# SimpleNode31.net
KiCad netlist of a schematic drawn in Altium Designer
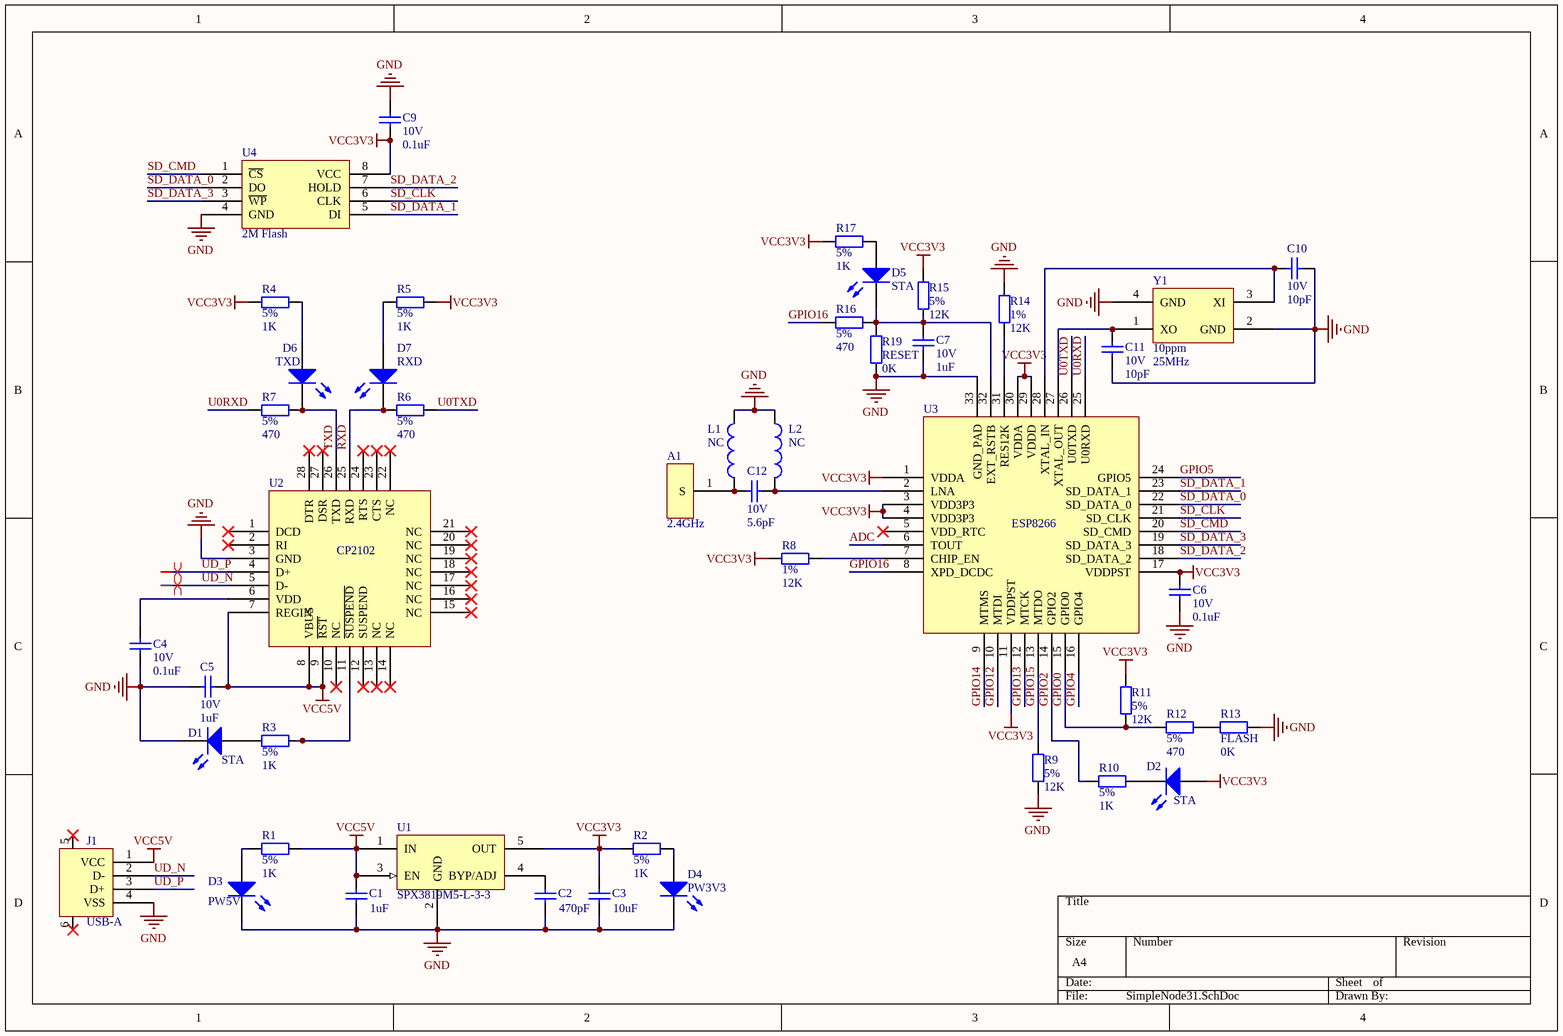
[diagram p0: SimpleNode31.SchDoc]

(export (version "E")
  (design (tool "Eeschema 10.0.6"))
  (components
    (comp (ref "A1")
      (value "2.4GHz")
      (footprint "AN9520-245")
      (description "贴片2.4G陶瓷天线")
      (libsource (lib "基础元器件") (part "AN9520-245"))
    )
    (comp (ref "C1")
      (value "1uF")
      (footprint "C0402")
      (description "贴片无极性电容")
      (fields (field (name "Comment") "105"))
      (libsource (lib "基础元器件") (part "贴片无极性电容"))
    )
    (comp (ref "C2")
      (value "470pF")
      (footprint "C0402")
      (description "贴片无极性电容")
      (fields (field (name "Comment") "CAP"))
      (libsource (lib "基础元器件") (part "贴片无极性电容"))
    )
    (comp (ref "C3")
      (value "10uF")
      (footprint "C0402")
      (description "贴片无极性电容")
      (fields (field (name "Comment") "CAP"))
      (libsource (lib "基础元器件") (part "贴片无极性电容"))
    )
    (comp (ref "C4")
      (value "10V")
      (footprint "C0402")
      (description "贴片无极性电容")
      (fields (field (name "ALTIUM_VALUE") "0.1uF"))
      (libsource (lib "基础元器件") (part "贴片无极性电容"))
    )
    (comp (ref "C5")
      (value "10V")
      (footprint "C0402")
      (description "贴片无极性电容")
      (fields (field (name "ALTIUM_VALUE") "1uF"))
      (libsource (lib "基础元器件") (part "贴片无极性电容"))
    )
    (comp (ref "C6")
      (value "10V")
      (footprint "C0402")
      (description "贴片无极性电容")
      (fields (field (name "ALTIUM_VALUE") "0.1uF"))
      (libsource (lib "基础元器件") (part "贴片无极性电容"))
    )
    (comp (ref "C7")
      (value "10V")
      (footprint "C0402")
      (description "贴片无极性电容")
      (fields (field (name "ALTIUM_VALUE") "1uF"))
      (libsource (lib "基础元器件") (part "贴片无极性电容"))
    )
    (comp (ref "C9")
      (value "10V")
      (footprint "C0402")
      (description "贴片无极性电容")
      (fields (field (name "ALTIUM_VALUE") "0.1uF"))
      (libsource (lib "基础元器件") (part "贴片无极性电容"))
    )
    (comp (ref "C10")
      (value "10V")
      (footprint "C0402")
      (description "贴片无极性电容")
      (fields (field (name "ALTIUM_VALUE") "10pF"))
      (libsource (lib "基础元器件") (part "贴片无极性电容"))
    )
    (comp (ref "C11")
      (value "10V")
      (footprint "C0402")
      (description "贴片无极性电容")
      (fields (field (name "ALTIUM_VALUE") "10pF"))
      (libsource (lib "基础元器件") (part "贴片无极性电容"))
    )
    (comp (ref "C12")
      (value "10V")
      (footprint "C0402")
      (description "贴片无极性电容")
      (fields (field (name "ALTIUM_VALUE") "5.6pF"))
      (libsource (lib "基础元器件") (part "贴片无极性电容"))
    )
    (comp (ref "D1")
      (value "STA")
      (footprint "LED0402")
      (description "贴片发光二级管")
      (libsource (lib "基础元器件") (part "贴片发光二级管"))
    )
    (comp (ref "D2")
      (value "STA")
      (footprint "LED0402")
      (description "贴片发光二级管")
      (libsource (lib "基础元器件") (part "贴片发光二级管"))
    )
    (comp (ref "D3")
      (value "PW5V")
      (footprint "LED0402")
      (description "贴片发光二级管")
      (libsource (lib "基础元器件") (part "贴片发光二级管"))
    )
    (comp (ref "D4")
      (value "PW3V3")
      (footprint "LED0402")
      (description "贴片发光二级管")
      (libsource (lib "基础元器件") (part "贴片发光二级管"))
    )
    (comp (ref "D5")
      (value "STA")
      (footprint "LED0402")
      (description "贴片发光二级管")
      (libsource (lib "基础元器件") (part "贴片发光二级管"))
    )
    (comp (ref "D6")
      (value "TXD")
      (footprint "LED0402")
      (description "贴片发光二级管")
      (libsource (lib "基础元器件") (part "贴片发光二级管"))
    )
    (comp (ref "D7")
      (value "RXD")
      (footprint "LED0402")
      (description "贴片发光二级管")
      (libsource (lib "基础元器件") (part "贴片发光二级管"))
    )
    (comp (ref "J1")
      (value "USB-A")
      (footprint "USB 2.0 Type A 公头 沉板")
      (description "USB-A 公头")
      (libsource (lib "基础连接件") (part "USB-A 公头"))
    )
    (comp (ref "L1")
      (value "NC")
      (footprint "L0402")
      (description "贴片电感")
      (libsource (lib "") (part "贴片电感_1"))
    )
    (comp (ref "L2")
      (value "NC")
      (footprint "L0402")
      (description "贴片电感")
      (libsource (lib "基础元器件") (part "贴片电感"))
    )
    (comp (ref "R1")
      (value "5%")
      (footprint "R0402")
      (description "贴片电阻")
      (fields (field (name "ALTIUM_VALUE") "1K"))
      (libsource (lib "基础元器件") (part "贴片电阻"))
    )
    (comp (ref "R2")
      (value "5%")
      (footprint "R0402")
      (description "贴片电阻")
      (fields (field (name "ALTIUM_VALUE") "1K"))
      (libsource (lib "基础元器件") (part "贴片电阻"))
    )
    (comp (ref "R3")
      (value "5%")
      (footprint "R0402")
      (description "贴片电阻")
      (fields (field (name "ALTIUM_VALUE") "1K"))
      (libsource (lib "基础元器件") (part "贴片电阻"))
    )
    (comp (ref "R4")
      (value "5%")
      (footprint "R0402")
      (description "贴片电阻")
      (fields (field (name "ALTIUM_VALUE") "1K"))
      (libsource (lib "基础元器件") (part "贴片电阻"))
    )
    (comp (ref "R5")
      (value "5%")
      (footprint "R0402")
      (description "贴片电阻")
      (fields (field (name "ALTIUM_VALUE") "1K"))
      (libsource (lib "基础元器件") (part "贴片电阻"))
    )
    (comp (ref "R6")
      (value "5%")
      (footprint "R0402")
      (description "贴片电阻")
      (fields (field (name "ALTIUM_VALUE") "470"))
      (libsource (lib "基础元器件") (part "贴片电阻"))
    )
    (comp (ref "R7")
      (value "5%")
      (footprint "R0402")
      (description "贴片电阻")
      (fields (field (name "ALTIUM_VALUE") "470"))
      (libsource (lib "基础元器件") (part "贴片电阻"))
    )
    (comp (ref "R8")
      (value "1%")
      (footprint "R0402")
      (description "贴片电阻")
      (fields (field (name "ALTIUM_VALUE") "12K"))
      (libsource (lib "") (part "贴片电阻_1"))
    )
    (comp (ref "R9")
      (value "5%")
      (footprint "R0402")
      (description "贴片电阻")
      (fields (field (name "ALTIUM_VALUE") "12K"))
      (libsource (lib "") (part "贴片电阻_2"))
    )
    (comp (ref "R10")
      (value "5%")
      (footprint "R0402")
      (description "贴片电阻")
      (fields (field (name "ALTIUM_VALUE") "1K"))
      (libsource (lib "基础元器件") (part "贴片电阻"))
    )
    (comp (ref "R11")
      (value "5%")
      (footprint "R0402")
      (description "贴片电阻")
      (fields (field (name "ALTIUM_VALUE") "12K"))
      (libsource (lib "") (part "贴片电阻_2"))
    )
    (comp (ref "R12")
      (value "5%")
      (footprint "R0402")
      (description "贴片电阻")
      (fields (field (name "ALTIUM_VALUE") "470"))
      (libsource (lib "") (part "贴片电阻_1"))
    )
    (comp (ref "R13")
      (value "FLASH")
      (footprint "R0402")
      (description "贴片电阻")
      (fields (field (name "ALTIUM_VALUE") "0K"))
      (libsource (lib "基础元器件") (part "贴片电阻"))
    )
    (comp (ref "R14")
      (value "1%")
      (footprint "R0402")
      (description "贴片电阻")
      (fields (field (name "ALTIUM_VALUE") "12K"))
      (libsource (lib "") (part "贴片电阻_2"))
    )
    (comp (ref "R15")
      (value "5%")
      (footprint "R0402")
      (description "贴片电阻")
      (fields (field (name "ALTIUM_VALUE") "12K"))
      (libsource (lib "") (part "贴片电阻_2"))
    )
    (comp (ref "R16")
      (value "5%")
      (footprint "R0402")
      (description "贴片电阻")
      (fields (field (name "ALTIUM_VALUE") "470"))
      (libsource (lib "基础元器件") (part "贴片电阻"))
    )
    (comp (ref "R17")
      (value "5%")
      (footprint "R0402")
      (description "贴片电阻")
      (fields (field (name "ALTIUM_VALUE") "1K"))
      (libsource (lib "") (part "贴片电阻_1"))
    )
    (comp (ref "R19")
      (value "RESET")
      (footprint "R0402")
      (description "贴片电阻")
      (fields (field (name "ALTIUM_VALUE") "0K"))
      (libsource (lib "") (part "贴片电阻_2"))
    )
    (comp (ref "U1")
      (value "SPX3819M5-L-3-3")
      (footprint "SOT25-5")
      (description "贴片5V转3.3V芯片")
      (libsource (lib "基础元器件") (part "SPX3819M5-L-3-3"))
    )
    (comp (ref "U2")
      (value "CP2102")
      (footprint "MLP28")
      (description "贴片USB转TTL")
      (libsource (lib "基础元器件") (part "CP2102"))
    )
    (comp (ref "U3")
      (value "ESP8266")
      (footprint "QFN32L")
      (description "ESP8266无线WiFi芯片")
      (libsource (lib "基础元器件") (part "ESP8266"))
    )
    (comp (ref "U4")
      (value "2M Flash")
      (footprint "SOP8")
      (description "贴片2M存储Flash芯片")
      (libsource (lib "基础元器件") (part "GD25Q16CSIG"))
    )
    (comp (ref "Y1")
      (value "10ppm")
      (footprint "XTAL-2520")
      (description "贴片无源晶振")
      (fields (field (name "ALTIUM_VALUE") "25MHz"))
      (libsource (lib "基础元器件") (part "贴片无源晶振"))
    )
  )
  (nets
    (net (code "1") (name "/ADC") (class "Default")
      (node (ref "U3") (pin "6") (pinfunction "TOUT_6") (pintype "passive"))
    )
    (net (code "2") (name "/GPIO0") (class "Default")
      (node (ref "R11") (pin "1") (pinfunction "1_1") (pintype "passive"))
      (node (ref "R12") (pin "1") (pinfunction "1_1") (pintype "passive"))
      (node (ref "U3") (pin "15") (pinfunction "GPIO0_15") (pintype "passive"))
    )
    (net (code "3") (name "/GPIO2") (class "Default")
      (node (ref "R10") (pin "2") (pinfunction "2_2") (pintype "passive"))
      (node (ref "U3") (pin "14") (pinfunction "GPIO2_14") (pintype "passive"))
    )
    (net (code "4") (name "/GPIO4") (class "Default")
      (node (ref "U3") (pin "16") (pinfunction "GPIO4_16") (pintype "passive"))
    )
    (net (code "5") (name "/GPIO5") (class "Default")
      (node (ref "U3") (pin "24") (pinfunction "GPIO5_24") (pintype "passive"))
    )
    (net (code "6") (name "/GPIO12") (class "Default")
      (node (ref "U3") (pin "10") (pinfunction "MTDI_10") (pintype "passive"))
    )
    (net (code "7") (name "/GPIO13") (class "Default")
      (node (ref "U3") (pin "12") (pinfunction "MTCK_12") (pintype "passive"))
    )
    (net (code "8") (name "/GPIO14") (class "Default")
      (node (ref "U3") (pin "9") (pinfunction "MTMS_9") (pintype "passive"))
    )
    (net (code "9") (name "/GPIO15") (class "Default")
      (node (ref "R9") (pin "2") (pinfunction "2_2") (pintype "passive"))
      (node (ref "U3") (pin "13") (pinfunction "MTDO_13") (pintype "passive"))
    )
    (net (code "10") (name "/GPIO16") (class "Default")
      (node (ref "R16") (pin "2") (pinfunction "2_2") (pintype "passive"))
      (node (ref "U3") (pin "8") (pinfunction "XPD_DCDC_8") (pintype "passive"))
    )
    (net (code "11") (name "/RXD") (class "Default")
      (node (ref "D7") (pin "2") (pinfunction "K_2") (pintype "passive"))
      (node (ref "R6") (pin "2") (pinfunction "2_2") (pintype "passive"))
      (node (ref "U2") (pin "25") (pinfunction "RXD_25") (pintype "passive"))
    )
    (net (code "12") (name "/SD_CLK") (class "Default")
      (node (ref "U3") (pin "21") (pinfunction "SD_CLK_21") (pintype "passive"))
      (node (ref "U4") (pin "6") (pinfunction "CLK_6") (pintype "passive"))
    )
    (net (code "13") (name "/SD_CMD") (class "Default")
      (node (ref "U3") (pin "20") (pinfunction "SD_CMD_20") (pintype "passive"))
      (node (ref "U4") (pin "1") (pinfunction "~{CS}_1") (pintype "passive"))
    )
    (net (code "14") (name "/SD_DATA_0") (class "Default")
      (node (ref "U3") (pin "22") (pinfunction "SD_DATA_0_22") (pintype "passive"))
      (node (ref "U4") (pin "2") (pinfunction "DO_2") (pintype "passive"))
    )
    (net (code "15") (name "/SD_DATA_1") (class "Default")
      (node (ref "U3") (pin "23") (pinfunction "SD_DATA_1_23") (pintype "passive"))
      (node (ref "U4") (pin "5") (pinfunction "DI_5") (pintype "passive"))
    )
    (net (code "16") (name "/SD_DATA_2") (class "Default")
      (node (ref "U3") (pin "18") (pinfunction "SD_DATA_2_18") (pintype "passive"))
      (node (ref "U4") (pin "7") (pinfunction "HOLD_7") (pintype "passive"))
    )
    (net (code "17") (name "/SD_DATA_3") (class "Default")
      (node (ref "U3") (pin "19") (pinfunction "SD_DATA_3_19") (pintype "passive"))
      (node (ref "U4") (pin "3") (pinfunction "~{WP}_3") (pintype "passive"))
    )
    (net (code "18") (name "/TXD") (class "Default")
      (node (ref "D6") (pin "2") (pinfunction "K_2") (pintype "passive"))
      (node (ref "R7") (pin "1") (pinfunction "1_1") (pintype "passive"))
      (node (ref "U2") (pin "26") (pinfunction "TXD_26") (pintype "passive"))
    )
    (net (code "19") (name "/U0RXD") (class "Default")
      (node (ref "R7") (pin "2") (pinfunction "2_2") (pintype "passive"))
      (node (ref "U3") (pin "25") (pinfunction "U0RXD_25") (pintype "passive"))
    )
    (net (code "20") (name "/U0TXD") (class "Default")
      (node (ref "R6") (pin "1") (pinfunction "1_1") (pintype "passive"))
      (node (ref "U3") (pin "26") (pinfunction "U0TXD_26") (pintype "passive"))
    )
    (net (code "21") (name "/UD_N") (class "Default")
      (node (ref "J1") (pin "2") (pinfunction "D-_2") (pintype "passive"))
      (node (ref "U2") (pin "5") (pinfunction "D-_5") (pintype "passive"))
    )
    (net (code "22") (name "/UD_P") (class "Default")
      (node (ref "J1") (pin "3") (pinfunction "D+_3") (pintype "passive"))
      (node (ref "U2") (pin "4") (pinfunction "D+_4") (pintype "passive"))
    )
    (net (code "23") (name "GND") (class "Default")
      (node (ref "C1") (pin "1") (pinfunction "1_1") (pintype "passive"))
      (node (ref "C10") (pin "2") (pinfunction "2_2") (pintype "passive"))
      (node (ref "C11") (pin "2") (pinfunction "2_2") (pintype "passive"))
      (node (ref "C2") (pin "1") (pinfunction "1_1") (pintype "passive"))
      (node (ref "C3") (pin "1") (pinfunction "1_1") (pintype "passive"))
      (node (ref "C4") (pin "1") (pinfunction "1_1") (pintype "passive"))
      (node (ref "C5") (pin "2") (pinfunction "2_2") (pintype "passive"))
      (node (ref "C6") (pin "1") (pinfunction "1_1") (pintype "passive"))
      (node (ref "C7") (pin "1") (pinfunction "1_1") (pintype "passive"))
      (node (ref "C9") (pin "1") (pinfunction "1_1") (pintype "passive"))
      (node (ref "D1") (pin "2") (pinfunction "K_2") (pintype "passive"))
      (node (ref "D3") (pin "2") (pinfunction "K_2") (pintype "passive"))
      (node (ref "D4") (pin "2") (pinfunction "K_2") (pintype "passive"))
      (node (ref "J1") (pin "4") (pinfunction "VSS_4") (pintype "passive"))
      (node (ref "L1") (pin "2") (pinfunction "2_2") (pintype "passive"))
      (node (ref "L2") (pin "2") (pinfunction "2_2") (pintype "passive"))
      (node (ref "R13") (pin "1") (pinfunction "1_1") (pintype "passive"))
      (node (ref "R14") (pin "2") (pinfunction "2_2") (pintype "passive"))
      (node (ref "R19") (pin "1") (pinfunction "1_1") (pintype "passive"))
      (node (ref "R9") (pin "1") (pinfunction "1_1") (pintype "passive"))
      (node (ref "U1") (pin "2") (pinfunction "GND_2") (pintype "power_in"))
      (node (ref "U2") (pin "3") (pinfunction "GND_3") (pintype "passive"))
      (node (ref "U3") (pin "33") (pinfunction "GND_PAD_33") (pintype "passive"))
      (node (ref "U4") (pin "4") (pinfunction "GND_4") (pintype "passive"))
      (node (ref "Y1") (pin "2") (pinfunction "GND_2") (pintype "passive"))
      (node (ref "Y1") (pin "4") (pinfunction "GND_4") (pintype "passive"))
    )
    (net (code "24") (name "Net-(A1-S)") (class "Default")
      (node (ref "A1") (pin "1") (pinfunction "S_1") (pintype "passive"))
      (node (ref "C12") (pin "1") (pinfunction "1_1") (pintype "passive"))
      (node (ref "L1") (pin "1") (pinfunction "1_1") (pintype "passive"))
    )
    (net (code "25") (name "Net-(D1-A)") (class "Default")
      (node (ref "D1") (pin "1") (pinfunction "A_1") (pintype "passive"))
      (node (ref "R3") (pin "2") (pinfunction "2_2") (pintype "passive"))
    )
    (net (code "26") (name "Net-(D2-K)") (class "Default")
      (node (ref "D2") (pin "2") (pinfunction "K_2") (pintype "passive"))
      (node (ref "R10") (pin "1") (pinfunction "1_1") (pintype "passive"))
    )
    (net (code "27") (name "Net-(D3-A)") (class "Default")
      (node (ref "D3") (pin "1") (pinfunction "A_1") (pintype "passive"))
      (node (ref "R1") (pin "2") (pinfunction "2_2") (pintype "passive"))
    )
    (net (code "28") (name "Net-(D4-A)") (class "Default")
      (node (ref "D4") (pin "1") (pinfunction "A_1") (pintype "passive"))
      (node (ref "R2") (pin "1") (pinfunction "1_1") (pintype "passive"))
    )
    (net (code "29") (name "Net-(D5-A)") (class "Default")
      (node (ref "D5") (pin "1") (pinfunction "A_1") (pintype "passive"))
      (node (ref "R17") (pin "2") (pinfunction "2_2") (pintype "passive"))
    )
    (net (code "30") (name "Net-(D5-K)") (class "Default")
      (node (ref "C7") (pin "2") (pinfunction "2_2") (pintype "passive"))
      (node (ref "D5") (pin "2") (pinfunction "K_2") (pintype "passive"))
      (node (ref "R15") (pin "1") (pinfunction "1_1") (pintype "passive"))
      (node (ref "R16") (pin "1") (pinfunction "1_1") (pintype "passive"))
      (node (ref "R19") (pin "2") (pinfunction "2_2") (pintype "passive"))
      (node (ref "U3") (pin "32") (pinfunction "EXT_RSTB_32") (pintype "passive"))
    )
    (net (code "31") (name "Net-(D6-A)") (class "Default")
      (node (ref "D6") (pin "1") (pinfunction "A_1") (pintype "passive"))
      (node (ref "R4") (pin "1") (pinfunction "1_1") (pintype "passive"))
    )
    (net (code "32") (name "Net-(D7-A)") (class "Default")
      (node (ref "D7") (pin "1") (pinfunction "A_1") (pintype "passive"))
      (node (ref "R5") (pin "2") (pinfunction "2_2") (pintype "passive"))
    )
    (net (code "33") (name "Net-(R12-Pad2)") (class "Default")
      (node (ref "R12") (pin "2") (pinfunction "2_2") (pintype "passive"))
      (node (ref "R13") (pin "2") (pinfunction "2_2") (pintype "passive"))
    )
    (net (code "34") (name "Net-(U1-BYP{slash}ADJ)") (class "Default")
      (node (ref "C2") (pin "2") (pinfunction "2_2") (pintype "passive"))
      (node (ref "U1") (pin "4") (pinfunction "BYP/ADJ_4") (pintype "passive"))
    )
    (net (code "35") (name "Net-(U2-VDD)") (class "Default")
      (node (ref "C4") (pin "2") (pinfunction "2_2") (pintype "passive"))
      (node (ref "U2") (pin "6") (pinfunction "VDD_6") (pintype "passive"))
    )
    (net (code "36") (name "Net-(U2-~{SUSPEND})") (class "Default")
      (node (ref "R3") (pin "1") (pinfunction "1_1") (pintype "passive"))
      (node (ref "U2") (pin "11") (pinfunction "~{SUSPEND}_11") (pintype "passive"))
    )
    (net (code "37") (name "Net-(U3-CHIP_EN)") (class "Default")
      (node (ref "R8") (pin "2") (pinfunction "2_2") (pintype "passive"))
      (node (ref "U3") (pin "7") (pinfunction "CHIP_EN_7") (pintype "passive"))
    )
    (net (code "38") (name "Net-(U3-LNA)") (class "Default")
      (node (ref "C12") (pin "2") (pinfunction "2_2") (pintype "passive"))
      (node (ref "L2") (pin "1") (pinfunction "1_1") (pintype "passive"))
      (node (ref "U3") (pin "2") (pinfunction "LNA_2") (pintype "passive"))
    )
    (net (code "39") (name "Net-(U3-RES12K)") (class "Default")
      (node (ref "R14") (pin "1") (pinfunction "1_1") (pintype "passive"))
      (node (ref "U3") (pin "31") (pinfunction "RES12K_31") (pintype "passive"))
    )
    (net (code "40") (name "Net-(U3-XTAL_IN)") (class "Default")
      (node (ref "C10") (pin "1") (pinfunction "1_1") (pintype "passive"))
      (node (ref "U3") (pin "28") (pinfunction "XTAL_IN_28") (pintype "passive"))
      (node (ref "Y1") (pin "3") (pinfunction "XI_3") (pintype "passive"))
    )
    (net (code "41") (name "Net-(U3-XTAL_OUT)") (class "Default")
      (node (ref "C11") (pin "1") (pinfunction "1_1") (pintype "passive"))
      (node (ref "U3") (pin "27") (pinfunction "XTAL_OUT_27") (pintype "passive"))
      (node (ref "Y1") (pin "1") (pinfunction "XO_1") (pintype "passive"))
    )
    (net (code "42") (name "VCC3V3") (class "Default")
      (node (ref "C3") (pin "2") (pinfunction "2_2") (pintype "passive"))
      (node (ref "C6") (pin "2") (pinfunction "2_2") (pintype "passive"))
      (node (ref "C9") (pin "2") (pinfunction "2_2") (pintype "passive"))
      (node (ref "D2") (pin "1") (pinfunction "A_1") (pintype "passive"))
      (node (ref "R11") (pin "2") (pinfunction "2_2") (pintype "passive"))
      (node (ref "R15") (pin "2") (pinfunction "2_2") (pintype "passive"))
      (node (ref "R17") (pin "1") (pinfunction "1_1") (pintype "passive"))
      (node (ref "R2") (pin "2") (pinfunction "2_2") (pintype "passive"))
      (node (ref "R4") (pin "2") (pinfunction "2_2") (pintype "passive"))
      (node (ref "R5") (pin "1") (pinfunction "1_1") (pintype "passive"))
      (node (ref "R8") (pin "1") (pinfunction "1_1") (pintype "passive"))
      (node (ref "U1") (pin "5") (pinfunction "OUT_5") (pintype "power_in"))
      (node (ref "U3") (pin "1") (pinfunction "VDDA_1") (pintype "passive"))
      (node (ref "U3") (pin "11") (pinfunction "VDDPST_11") (pintype "passive"))
      (node (ref "U3") (pin "17") (pinfunction "VDDPST_17") (pintype "passive"))
      (node (ref "U3") (pin "29") (pinfunction "VDDD_29") (pintype "passive"))
      (node (ref "U3") (pin "3") (pinfunction "VDD3P3_3") (pintype "passive"))
      (node (ref "U3") (pin "30") (pinfunction "VDDA_30") (pintype "passive"))
      (node (ref "U3") (pin "4") (pinfunction "VDD3P3_4") (pintype "passive"))
      (node (ref "U4") (pin "8") (pinfunction "VCC_8") (pintype "power_in"))
    )
    (net (code "43") (name "VCC5V") (class "Default")
      (node (ref "C1") (pin "2") (pinfunction "2_2") (pintype "passive"))
      (node (ref "C5") (pin "1") (pinfunction "1_1") (pintype "passive"))
      (node (ref "J1") (pin "1") (pinfunction "VCC_1") (pintype "passive"))
      (node (ref "R1") (pin "1") (pinfunction "1_1") (pintype "passive"))
      (node (ref "U1") (pin "1") (pinfunction "IN_1") (pintype "power_in"))
      (node (ref "U1") (pin "3") (pinfunction "EN_3") (pintype "input"))
      (node (ref "U2") (pin "7") (pinfunction "REGIN_7") (pintype "passive"))
      (node (ref "U2") (pin "8") (pinfunction "VBUS_8") (pintype "passive"))
      (node (ref "U2") (pin "9") (pinfunction "~{RST}_9") (pintype "passive"))
    )
    (net (code "44") (name "unconnected-(J1-Pad5)") (class "Default")
      (node (ref "J1") (pin "5") (pinfunction "5_5") (pintype "passive+no_connect"))
    )
    (net (code "45") (name "unconnected-(J1-Pad6)") (class "Default")
      (node (ref "J1") (pin "6") (pinfunction "6_6") (pintype "passive+no_connect"))
    )
    (net (code "46") (name "unconnected-(U2-CTS-Pad23)") (class "Default")
      (node (ref "U2") (pin "23") (pinfunction "CTS_23") (pintype "passive+no_connect"))
    )
    (net (code "47") (name "unconnected-(U2-DCD-Pad1)") (class "Default")
      (node (ref "U2") (pin "1") (pinfunction "DCD_1") (pintype "passive+no_connect"))
    )
    (net (code "48") (name "unconnected-(U2-DSR-Pad27)") (class "Default")
      (node (ref "U2") (pin "27") (pinfunction "DSR_27") (pintype "passive+no_connect"))
    )
    (net (code "49") (name "unconnected-(U2-DTR-Pad28)") (class "Default")
      (node (ref "U2") (pin "28") (pinfunction "DTR_28") (pintype "passive+no_connect"))
    )
    (net (code "50") (name "unconnected-(U2-NC-Pad10)") (class "Default")
      (node (ref "U2") (pin "10") (pinfunction "NC_10") (pintype "passive+no_connect"))
    )
    (net (code "51") (name "unconnected-(U2-NC-Pad13)") (class "Default")
      (node (ref "U2") (pin "13") (pinfunction "NC_13") (pintype "passive+no_connect"))
    )
    (net (code "52") (name "unconnected-(U2-NC-Pad14)") (class "Default")
      (node (ref "U2") (pin "14") (pinfunction "NC_14") (pintype "passive+no_connect"))
    )
    (net (code "53") (name "unconnected-(U2-NC-Pad15)") (class "Default")
      (node (ref "U2") (pin "15") (pinfunction "NC_15") (pintype "passive+no_connect"))
    )
    (net (code "54") (name "unconnected-(U2-NC-Pad16)") (class "Default")
      (node (ref "U2") (pin "16") (pinfunction "NC_16") (pintype "passive+no_connect"))
    )
    (net (code "55") (name "unconnected-(U2-NC-Pad17)") (class "Default")
      (node (ref "U2") (pin "17") (pinfunction "NC_17") (pintype "passive+no_connect"))
    )
    (net (code "56") (name "unconnected-(U2-NC-Pad18)") (class "Default")
      (node (ref "U2") (pin "18") (pinfunction "NC_18") (pintype "passive+no_connect"))
    )
    (net (code "57") (name "unconnected-(U2-NC-Pad19)") (class "Default")
      (node (ref "U2") (pin "19") (pinfunction "NC_19") (pintype "passive+no_connect"))
    )
    (net (code "58") (name "unconnected-(U2-NC-Pad20)") (class "Default")
      (node (ref "U2") (pin "20") (pinfunction "NC_20") (pintype "passive+no_connect"))
    )
    (net (code "59") (name "unconnected-(U2-NC-Pad21)") (class "Default")
      (node (ref "U2") (pin "21") (pinfunction "NC_21") (pintype "passive+no_connect"))
    )
    (net (code "60") (name "unconnected-(U2-NC-Pad22)") (class "Default")
      (node (ref "U2") (pin "22") (pinfunction "NC_22") (pintype "passive+no_connect"))
    )
    (net (code "61") (name "unconnected-(U2-RI-Pad2)") (class "Default")
      (node (ref "U2") (pin "2") (pinfunction "RI_2") (pintype "passive+no_connect"))
    )
    (net (code "62") (name "unconnected-(U2-RTS-Pad24)") (class "Default")
      (node (ref "U2") (pin "24") (pinfunction "RTS_24") (pintype "passive+no_connect"))
    )
    (net (code "63") (name "unconnected-(U2-SUSPEND-Pad12)") (class "Default")
      (node (ref "U2") (pin "12") (pinfunction "SUSPEND_12") (pintype "passive+no_connect"))
    )
    (net (code "64") (name "unconnected-(U3-VDD_RTC-Pad5)") (class "Default")
      (node (ref "U3") (pin "5") (pinfunction "VDD_RTC_5") (pintype "passive+no_connect"))
    )
  )
)
